# gate_schematic.net
KiCad netlist of a schematic drawn in EAGLE
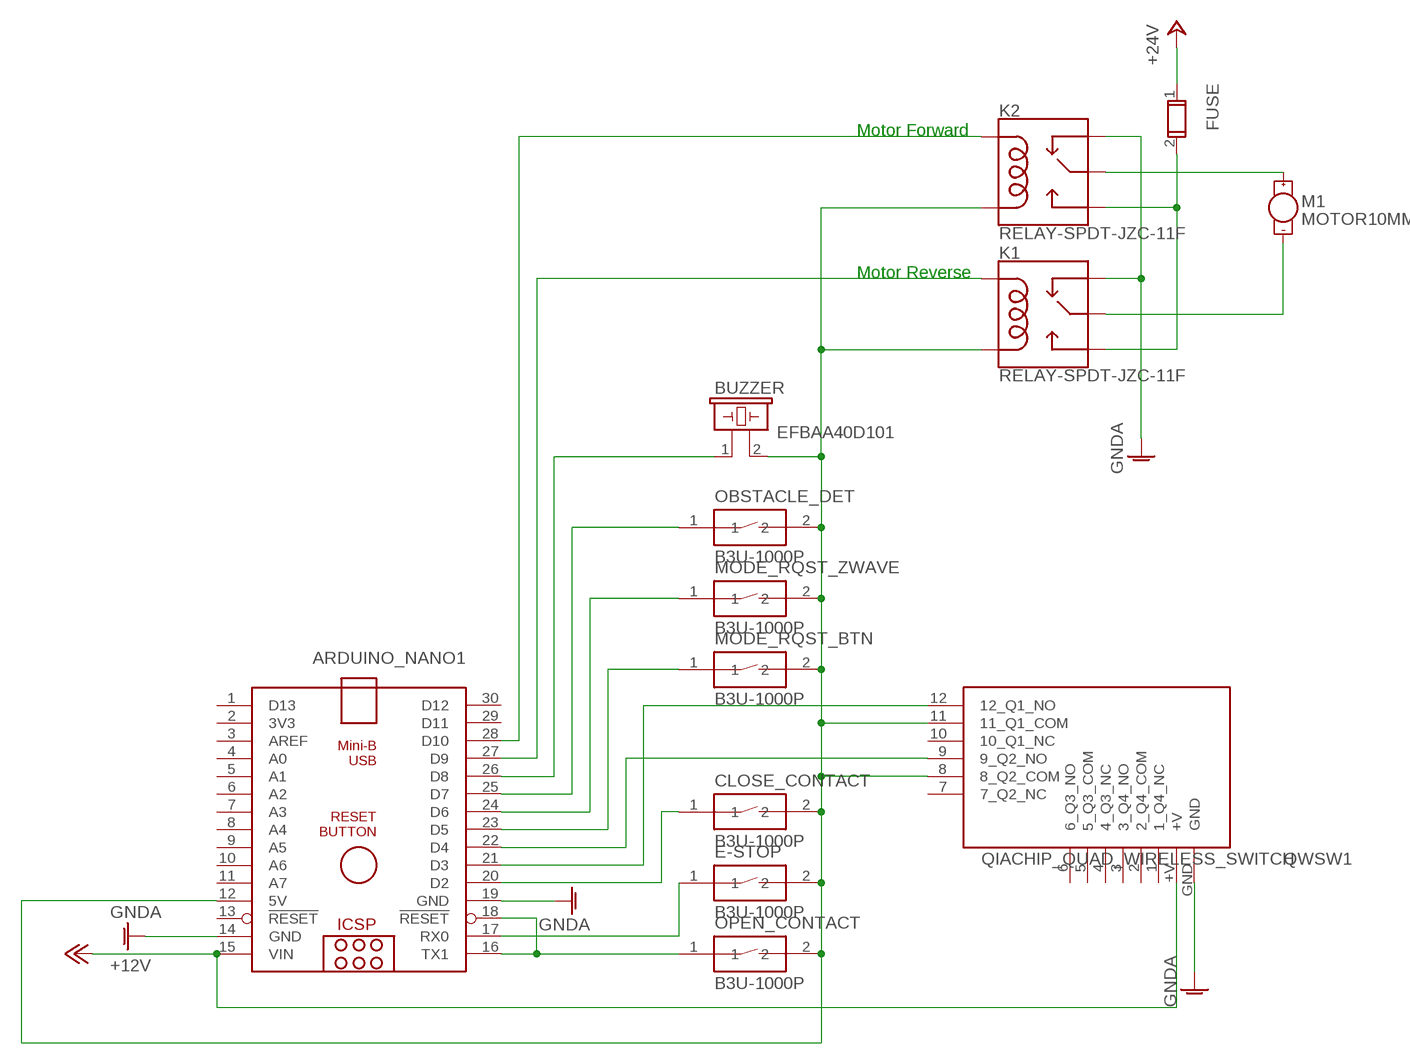
[diagram p0: schematic, sheet 1]

(export (version "E")
  (design (tool "Eeschema 10.0.6"))
  (components
    (comp (ref "ARDUINO_NANO1")
      (value "ARDUINO_NANO")
      (footprint "eagle-import:ARDUINO_NANO")
      (libsource (lib "eagle-import") (part "ARDUINO_NANO"))
    )
    (comp (ref "BUZZER")
      (value "EFBAA40D101")
      (footprint "eagle-import:EFBAA40D101")
      (libsource (lib "eagle-import") (part "EFB?AA40D101"))
    )
    (comp (ref "CLOSE_CONTACT")
      (value "B3U-1000P")
      (footprint "eagle-import:B3U-1000P")
      (fields
        (field (name "DIGI_KEY_PART_NUMBER") "SW1020CT-ND")
        (field (name "MANUFACTURER") "Omron Electronics Inc-EMC Div")
        (field (name "CREATED_BY") "PACBLAYOUT")
      )
      (libsource (lib "eagle-import") (part "B3U-1000P"))
    )
    (comp (ref "E-STOP")
      (value "B3U-1000P")
      (footprint "eagle-import:B3U-1000P")
      (fields
        (field (name "DIGI_KEY_PART_NUMBER") "SW1020CT-ND")
        (field (name "MANUFACTURER") "Omron Electronics Inc-EMC Div")
        (field (name "CREATED_BY") "PACBLAYOUT")
      )
      (libsource (lib "eagle-import") (part "B3U-1000P"))
    )
    (comp (ref "FUSE")
      (value "696106003002")
      (footprint "eagle-import:696106003002")
      (libsource (lib "eagle-import") (part "696106003002"))
    )
    (comp (ref "K1")
      (value "RELAY-SPDT-JZC-11F")
      (footprint "eagle-import:RELAY-JZC")
      (libsource (lib "eagle-import") (part "RELAY-SPDT-JZC-11F"))
    )
    (comp (ref "K2")
      (value "RELAY-SPDT-JZC-11F")
      (footprint "eagle-import:RELAY-JZC")
      (libsource (lib "eagle-import") (part "RELAY-SPDT-JZC-11F"))
    )
    (comp (ref "M1")
      (value "MOTOR10MM")
      (footprint "eagle-import:VIBE-MOTOR-10MM")
      (libsource (lib "eagle-import") (part "MOTOR10MM"))
    )
    (comp (ref "MODE_RQST_BTN")
      (value "B3U-1000P")
      (footprint "eagle-import:B3U-1000P")
      (fields
        (field (name "DIGI_KEY_PART_NUMBER") "SW1020CT-ND")
        (field (name "MANUFACTURER") "Omron Electronics Inc-EMC Div")
        (field (name "CREATED_BY") "PACBLAYOUT")
      )
      (libsource (lib "eagle-import") (part "B3U-1000P"))
    )
    (comp (ref "MODE_RQST_ZWAVE")
      (value "B3U-1000P")
      (footprint "eagle-import:B3U-1000P")
      (fields
        (field (name "DIGI_KEY_PART_NUMBER") "SW1020CT-ND")
        (field (name "MANUFACTURER") "Omron Electronics Inc-EMC Div")
        (field (name "CREATED_BY") "PACBLAYOUT")
      )
      (libsource (lib "eagle-import") (part "B3U-1000P"))
    )
    (comp (ref "OBSTACLE_DET")
      (value "B3U-1000P")
      (footprint "eagle-import:B3U-1000P")
      (fields
        (field (name "DIGI_KEY_PART_NUMBER") "SW1020CT-ND")
        (field (name "MANUFACTURER") "Omron Electronics Inc-EMC Div")
        (field (name "CREATED_BY") "PACBLAYOUT")
      )
      (libsource (lib "eagle-import") (part "B3U-1000P"))
    )
    (comp (ref "OPEN_CONTACT")
      (value "B3U-1000P")
      (footprint "eagle-import:B3U-1000P")
      (fields
        (field (name "DIGI_KEY_PART_NUMBER") "SW1020CT-ND")
        (field (name "MANUFACTURER") "Omron Electronics Inc-EMC Div")
        (field (name "CREATED_BY") "PACBLAYOUT")
      )
      (libsource (lib "eagle-import") (part "B3U-1000P"))
    )
    (comp (ref "QWSW1")
      (value "QIACHIP_QUAD_WIRELESS_SWITCH")
      (footprint "eagle-import:QIACHIP_QUAD_WIRELESS_SWITCH")
      (libsource (lib "eagle-import") (part "QIACHIP_QUAD_WIRELESS_SWITCH"))
    )
  )
  (nets
    (net (code "1") (name "+12V") (class "Default")
      (node (ref "ARDUINO_NANO1") (pin "15") (pinfunction "VIN_15") (pintype "power_in"))
      (node (ref "QWSW1") (pin "+V") (pinfunction "+V_+V") (pintype "bidirectional"))
    )
    (net (code "2") (name "+24V") (class "Default")
      (node (ref "FUSE") (pin "1") (pinfunction "1_1") (pintype "passive"))
    )
    (net (code "3") (name "GNDA") (class "Default")
      (node (ref "ARDUINO_NANO1") (pin "14") (pinfunction "GND_14") (pintype "power_in"))
      (node (ref "ARDUINO_NANO1") (pin "19") (pinfunction "GND_19") (pintype "power_in"))
      (node (ref "K1") (pin "2") (pinfunction "NC_2") (pintype "bidirectional"))
      (node (ref "K2") (pin "2") (pinfunction "NC_2") (pintype "bidirectional"))
      (node (ref "QWSW1") (pin "GND") (pinfunction "GND_GND") (pintype "bidirectional"))
    )
    (net (code "4") (name "Net-(ARDUINO_NANO1-5V)") (class "Default")
      (node (ref "ARDUINO_NANO1") (pin "12") (pinfunction "5V_12") (pintype "power_in"))
      (node (ref "BUZZER") (pin "2") (pinfunction "2_2") (pintype "passive"))
      (node (ref "CLOSE_CONTACT") (pin "2") (pinfunction "2_2") (pintype "passive"))
      (node (ref "E-STOP") (pin "2") (pinfunction "2_2") (pintype "passive"))
      (node (ref "K1") (pin "1") (pinfunction "COIL2_1") (pintype "bidirectional"))
      (node (ref "K2") (pin "1") (pinfunction "COIL2_1") (pintype "bidirectional"))
      (node (ref "MODE_RQST_BTN") (pin "2") (pinfunction "2_2") (pintype "passive"))
      (node (ref "MODE_RQST_ZWAVE") (pin "2") (pinfunction "2_2") (pintype "passive"))
      (node (ref "OBSTACLE_DET") (pin "2") (pinfunction "2_2") (pintype "passive"))
      (node (ref "OPEN_CONTACT") (pin "2") (pinfunction "2_2") (pintype "passive"))
      (node (ref "QWSW1") (pin "11") (pinfunction "11_Q1_COM_11") (pintype "bidirectional"))
      (node (ref "QWSW1") (pin "8") (pinfunction "8_Q2_COM_8") (pintype "bidirectional"))
    )
    (net (code "5") (name "Net-(ARDUINO_NANO1-D2)") (class "Default")
      (node (ref "ARDUINO_NANO1") (pin "20") (pinfunction "D2_20") (pintype "bidirectional"))
      (node (ref "CLOSE_CONTACT") (pin "1") (pinfunction "1_1") (pintype "passive"))
    )
    (net (code "6") (name "Net-(ARDUINO_NANO1-D3)") (class "Default")
      (node (ref "ARDUINO_NANO1") (pin "21") (pinfunction "D3_21") (pintype "bidirectional"))
      (node (ref "QWSW1") (pin "12") (pinfunction "12_Q1_NO_12") (pintype "bidirectional"))
    )
    (net (code "7") (name "Net-(ARDUINO_NANO1-D4)") (class "Default")
      (node (ref "ARDUINO_NANO1") (pin "22") (pinfunction "D4_22") (pintype "bidirectional"))
      (node (ref "QWSW1") (pin "9") (pinfunction "9_Q2_NO_9") (pintype "bidirectional"))
    )
    (net (code "8") (name "Net-(ARDUINO_NANO1-D5)") (class "Default")
      (node (ref "ARDUINO_NANO1") (pin "23") (pinfunction "D5_23") (pintype "bidirectional"))
      (node (ref "MODE_RQST_BTN") (pin "1") (pinfunction "1_1") (pintype "passive"))
    )
    (net (code "9") (name "Net-(ARDUINO_NANO1-D6)") (class "Default")
      (node (ref "ARDUINO_NANO1") (pin "24") (pinfunction "D6_24") (pintype "bidirectional"))
      (node (ref "MODE_RQST_ZWAVE") (pin "1") (pinfunction "1_1") (pintype "passive"))
    )
    (net (code "10") (name "Net-(ARDUINO_NANO1-D7)") (class "Default")
      (node (ref "ARDUINO_NANO1") (pin "25") (pinfunction "D7_25") (pintype "bidirectional"))
      (node (ref "OBSTACLE_DET") (pin "1") (pinfunction "1_1") (pintype "passive"))
    )
    (net (code "11") (name "Net-(ARDUINO_NANO1-D8)") (class "Default")
      (node (ref "ARDUINO_NANO1") (pin "26") (pinfunction "D8_26") (pintype "bidirectional"))
      (node (ref "BUZZER") (pin "1") (pinfunction "1_1") (pintype "passive"))
    )
    (net (code "12") (name "Net-(ARDUINO_NANO1-D9)") (class "Default")
      (node (ref "ARDUINO_NANO1") (pin "27") (pinfunction "D9_27") (pintype "bidirectional"))
      (node (ref "K1") (pin "5") (pinfunction "COIL1_5") (pintype "bidirectional"))
    )
    (net (code "13") (name "Net-(ARDUINO_NANO1-D10)") (class "Default")
      (node (ref "ARDUINO_NANO1") (pin "28") (pinfunction "D10_28") (pintype "bidirectional"))
      (node (ref "K2") (pin "5") (pinfunction "COIL1_5") (pintype "bidirectional"))
    )
    (net (code "14") (name "Net-(ARDUINO_NANO1-RX0)") (class "Default")
      (node (ref "ARDUINO_NANO1") (pin "17") (pinfunction "RX0_17") (pintype "bidirectional"))
      (node (ref "E-STOP") (pin "1") (pinfunction "1_1") (pintype "passive"))
    )
    (net (code "15") (name "Net-(ARDUINO_NANO1-TX1)") (class "Default")
      (node (ref "ARDUINO_NANO1") (pin "16") (pinfunction "TX1_16") (pintype "bidirectional"))
      (node (ref "ARDUINO_NANO1") (pin "18") (pinfunction "~{RESET}_18") (pintype "input"))
      (node (ref "OPEN_CONTACT") (pin "1") (pinfunction "1_1") (pintype "passive"))
    )
    (net (code "16") (name "Net-(K1-MAIN)") (class "Default")
      (node (ref "K1") (pin "4") (pinfunction "MAIN_4") (pintype "bidirectional"))
      (node (ref "M1") (pin "-") (pinfunction "-_-") (pintype "bidirectional"))
    )
    (net (code "17") (name "Net-(K1-NO)") (class "Default")
      (node (ref "FUSE") (pin "2") (pinfunction "2_2") (pintype "passive"))
      (node (ref "K1") (pin "3") (pinfunction "NO_3") (pintype "bidirectional"))
      (node (ref "K2") (pin "3") (pinfunction "NO_3") (pintype "bidirectional"))
    )
    (net (code "18") (name "Net-(K2-MAIN)") (class "Default")
      (node (ref "K2") (pin "4") (pinfunction "MAIN_4") (pintype "bidirectional"))
      (node (ref "M1") (pin "+") (pinfunction "+_+") (pintype "bidirectional"))
    )
    (net (code "19") (name "unconnected-(ARDUINO_NANO1-3V3-Pad2)") (class "Default")
      (node (ref "ARDUINO_NANO1") (pin "2") (pinfunction "3V3_2") (pintype "output"))
    )
    (net (code "20") (name "unconnected-(ARDUINO_NANO1-A0-Pad4)") (class "Default")
      (node (ref "ARDUINO_NANO1") (pin "4") (pinfunction "A0_4") (pintype "bidirectional"))
    )
    (net (code "21") (name "unconnected-(ARDUINO_NANO1-A1-Pad5)") (class "Default")
      (node (ref "ARDUINO_NANO1") (pin "5") (pinfunction "A1_5") (pintype "bidirectional"))
    )
    (net (code "22") (name "unconnected-(ARDUINO_NANO1-A2-Pad6)") (class "Default")
      (node (ref "ARDUINO_NANO1") (pin "6") (pinfunction "A2_6") (pintype "bidirectional"))
    )
    (net (code "23") (name "unconnected-(ARDUINO_NANO1-A3-Pad7)") (class "Default")
      (node (ref "ARDUINO_NANO1") (pin "7") (pinfunction "A3_7") (pintype "bidirectional"))
    )
    (net (code "24") (name "unconnected-(ARDUINO_NANO1-A4-Pad8)") (class "Default")
      (node (ref "ARDUINO_NANO1") (pin "8") (pinfunction "A4_8") (pintype "bidirectional"))
    )
    (net (code "25") (name "unconnected-(ARDUINO_NANO1-A5-Pad9)") (class "Default")
      (node (ref "ARDUINO_NANO1") (pin "9") (pinfunction "A5_9") (pintype "bidirectional"))
    )
    (net (code "26") (name "unconnected-(ARDUINO_NANO1-A6-Pad10)") (class "Default")
      (node (ref "ARDUINO_NANO1") (pin "10") (pinfunction "A6_10") (pintype "bidirectional"))
    )
    (net (code "27") (name "unconnected-(ARDUINO_NANO1-A7-Pad11)") (class "Default")
      (node (ref "ARDUINO_NANO1") (pin "11") (pinfunction "A7_11") (pintype "bidirectional"))
    )
    (net (code "28") (name "unconnected-(ARDUINO_NANO1-AREF-Pad3)") (class "Default")
      (node (ref "ARDUINO_NANO1") (pin "3") (pinfunction "AREF_3") (pintype "input"))
    )
    (net (code "29") (name "unconnected-(ARDUINO_NANO1-D11-Pad29)") (class "Default")
      (node (ref "ARDUINO_NANO1") (pin "29") (pinfunction "D11_29") (pintype "bidirectional"))
    )
    (net (code "30") (name "unconnected-(ARDUINO_NANO1-D12-Pad30)") (class "Default")
      (node (ref "ARDUINO_NANO1") (pin "30") (pinfunction "D12_30") (pintype "bidirectional"))
    )
    (net (code "31") (name "unconnected-(ARDUINO_NANO1-D13-Pad1)") (class "Default")
      (node (ref "ARDUINO_NANO1") (pin "1") (pinfunction "D13_1") (pintype "bidirectional"))
    )
    (net (code "32") (name "unconnected-(ARDUINO_NANO1-~{RESET}-Pad13)") (class "Default")
      (node (ref "ARDUINO_NANO1") (pin "13") (pinfunction "~{RESET}_13") (pintype "input"))
    )
    (net (code "33") (name "unconnected-(QWSW1-1_Q4_NC-Pad1)") (class "Default")
      (node (ref "QWSW1") (pin "1") (pinfunction "1_Q4_NC_1") (pintype "bidirectional"))
    )
    (net (code "34") (name "unconnected-(QWSW1-2_Q4_COM-Pad2)") (class "Default")
      (node (ref "QWSW1") (pin "2") (pinfunction "2_Q4_COM_2") (pintype "bidirectional"))
    )
    (net (code "35") (name "unconnected-(QWSW1-3_Q4_NO-Pad3)") (class "Default")
      (node (ref "QWSW1") (pin "3") (pinfunction "3_Q4_NO_3") (pintype "bidirectional"))
    )
    (net (code "36") (name "unconnected-(QWSW1-4_Q3_NC-Pad4)") (class "Default")
      (node (ref "QWSW1") (pin "4") (pinfunction "4_Q3_NC_4") (pintype "bidirectional"))
    )
    (net (code "37") (name "unconnected-(QWSW1-5_Q3_COM-Pad5)") (class "Default")
      (node (ref "QWSW1") (pin "5") (pinfunction "5_Q3_COM_5") (pintype "bidirectional"))
    )
    (net (code "38") (name "unconnected-(QWSW1-6_Q3_NO-Pad6)") (class "Default")
      (node (ref "QWSW1") (pin "6") (pinfunction "6_Q3_NO_6") (pintype "bidirectional"))
    )
    (net (code "39") (name "unconnected-(QWSW1-7_Q2_NC-Pad7)") (class "Default")
      (node (ref "QWSW1") (pin "7") (pinfunction "7_Q2_NC_7") (pintype "bidirectional"))
    )
    (net (code "40") (name "unconnected-(QWSW1-10_Q1_NC-Pad10)") (class "Default")
      (node (ref "QWSW1") (pin "10") (pinfunction "10_Q1_NC_10") (pintype "bidirectional"))
    )
  )
)
